# FOTA_Microcontroller_Power_Switch.net
KiCad netlist of a schematic drawn in Altium Designer
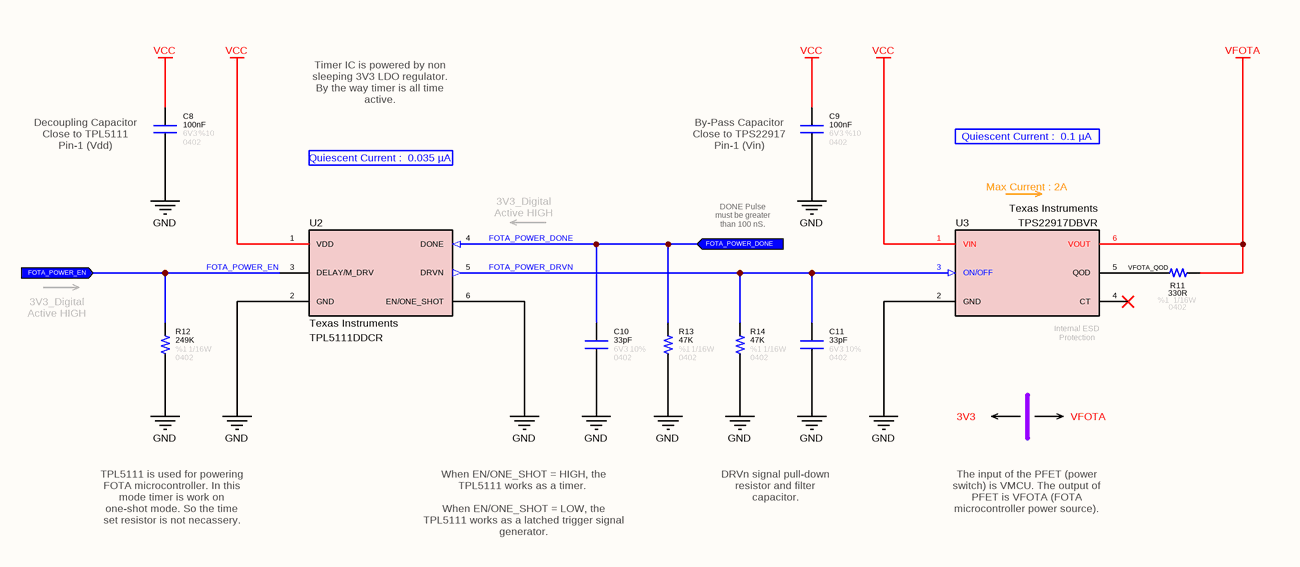
[diagram p0: FOTA Microcontroller Power Switch.SchDoc]

(export (version "E")
  (design (tool "Eeschema 10.0.6"))
  (components
    (comp (ref "C8")
      (value "100nF")
      (footprint "CAPACITOR_0402")
      (description "Capacitor - 100nF [0402-6V3] (Ceramic)")
      (fields
        (field (name "MANUFACTURER PART NUMBER") "04026D104KAT4A")
        (field (name "TOLERANCE") "%10")
        (field (name "VOLTAGE") "6V3")
        (field (name "CASE") "0402")
        (field (name "Comment") "Capacitor - 100nF [0402] (Ceramic)")
      )
      (libsource (lib "P101DA_Library") (part "Capacitor - 100nF [0402-6V3]"))
    )
    (comp (ref "C9")
      (value "100nF")
      (footprint "CAPACITOR_0402")
      (description "Capacitor - 100nF [0402-6V3] (Ceramic)")
      (fields
        (field (name "MANUFACTURER PART NUMBER") "04026D104KAT4A")
        (field (name "TOLERANCE") "%10")
        (field (name "VOLTAGE") "6V3")
        (field (name "CASE") "0402")
        (field (name "Comment") "Capacitor - 100nF [0402] (Ceramic)")
      )
      (libsource (lib "P101DA_Library") (part "Capacitor - 100nF [0402-6V3]"))
    )
    (comp (ref "C10")
      (value "33pF")
      (footprint "CAPACITOR_0402")
      (description "Capacitor - 33pF [0402] (Ceramic)")
      (fields
        (field (name "MANUFACTURER PART NUMBER") "C0402C330J9RACAUTO")
        (field (name "TOLERANCE") "10%")
        (field (name "CASE") "0402")
        (field (name "VOLTAGE") "6V3")
      )
      (libsource (lib "P101DA_Library") (part "Capacitor - 33pF [0402-6V3]"))
    )
    (comp (ref "C11")
      (value "33pF")
      (footprint "CAPACITOR_0402")
      (description "Capacitor - 33pF [0402] (Ceramic)")
      (fields
        (field (name "MANUFACTURER PART NUMBER") "C0402C330J9RACAUTO")
        (field (name "TOLERANCE") "10%")
        (field (name "CASE") "0402")
        (field (name "VOLTAGE") "6V3")
      )
      (libsource (lib "P101DA_Library") (part "Capacitor - 33pF [0402-6V3]"))
    )
    (comp (ref "R11")
      (value "330R")
      (footprint "RESISTOR_0402")
      (description "Thick Film Resistors - SMD 1/16 W 330 Ohm 1%")
      (fields
        (field (name "MANUFACTURER PART NUMBER") "CRCW0402330RFKED")
        (field (name "CASE") "0402")
        (field (name "TOLERANCE") "%1")
        (field (name "POWER") "1/16W")
        (field (name "Comment") "330R - 0402 - %1 - 1/16W")
      )
      (libsource (lib "P101DA_Library") (part "Resistor - 330R [0402]"))
    )
    (comp (ref "R12")
      (value "249K")
      (footprint "RESISTOR_0402")
      (description "Thick Film Resistors - SMD 1/16 W 249 KOhm 1%")
      (fields
        (field (name "MANUFACTURER PART NUMBER") "CRCW0402249KFKED")
        (field (name "POWER") "1/16W")
        (field (name "CASE") "0402")
        (field (name "TOLERANCE") "%1")
        (field (name "Comment") "249K - 0402 - %1 - 1/16W")
      )
      (libsource (lib "P101DA_Library") (part "Resistor - 249K [0402]"))
    )
    (comp (ref "R13")
      (value "47K")
      (footprint "RESISTOR_0402")
      (description "Thick Film Resistors - SMD 1/16 W 47 KOhm 1%")
      (fields
        (field (name "MANUFACTURER PART NUMBER") "CRCW040247K0FKED")
        (field (name "TOLERANCE") "%1")
        (field (name "CASE") "0402")
        (field (name "POWER") "1/16W")
        (field (name "Comment") "47K - 0402 - %1 - 1/16W")
      )
      (libsource (lib "P101DA_Library") (part "Resistor - 47K [0402]"))
    )
    (comp (ref "R14")
      (value "47K")
      (footprint "RESISTOR_0402")
      (description "Thick Film Resistors - SMD 1/16 W 47 KOhm 1%")
      (fields
        (field (name "MANUFACTURER PART NUMBER") "CRCW040247K0FKED")
        (field (name "TOLERANCE") "%1")
        (field (name "CASE") "0402")
        (field (name "POWER") "1/16W")
        (field (name "Comment") "47K - 0402 - %1 - 1/16W")
      )
      (libsource (lib "P101DA_Library") (part "Resistor - 47K [0402]"))
    )
    (comp (ref "U2")
      (value "TPL5111DDCR")
      (footprint "SOT-23-6")
      (description "NANO-POWER SYSTEM TIMER FOR POWE")
      (fields
        (field (name "MANUFACTURER NAME") "Texas Instruments")
        (field (name "MANUFACTURER PART NUMBER") "TPL5111DDCR")
      )
      (libsource (lib "P101DA_Library") (part "IC - TPL5111"))
    )
    (comp (ref "U3")
      (value "Power Switch")
      (footprint "SOT-23-6")
      (description "Power Switch MosFet")
      (fields
        (field (name "MANUFACTURER PART NUMBER") "TPS22917DBVR")
        (field (name "MANUFACTURER NAME") "Texas Instruments")
      )
      (libsource (lib "P101DA_Library") (part "IC - TPS22917"))
    )
  )
  (nets
    (net (code "1") (name "/FOTA_POWER_DONE") (class "Default")
      (node (ref "C10") (pin "2") (pinfunction "2_2") (pintype "passive"))
      (node (ref "R13") (pin "2") (pinfunction "2_2") (pintype "passive"))
      (node (ref "U2") (pin "4") (pinfunction "DONE_4") (pintype "input"))
    )
    (net (code "2") (name "/FOTA_POWER_DRVN") (class "Default")
      (node (ref "C11") (pin "2") (pinfunction "2_2") (pintype "passive"))
      (node (ref "R14") (pin "2") (pinfunction "2_2") (pintype "passive"))
      (node (ref "U2") (pin "5") (pinfunction "DRVN_5") (pintype "output"))
      (node (ref "U3") (pin "3") (pinfunction "ON/OFF_3") (pintype "input"))
    )
    (net (code "3") (name "/FOTA_POWER_EN") (class "Default")
      (node (ref "R12") (pin "2") (pinfunction "2_2") (pintype "passive"))
      (node (ref "U2") (pin "3") (pinfunction "DELAY/M_DRV_3") (pintype "passive"))
    )
    (net (code "4") (name "/VFOTA_QOD") (class "Default")
      (node (ref "R11") (pin "2") (pinfunction "2_2") (pintype "passive"))
      (node (ref "U3") (pin "5") (pinfunction "QOD_5") (pintype "power_in"))
    )
    (net (code "5") (name "GND") (class "Default")
      (node (ref "C10") (pin "1") (pinfunction "1_1") (pintype "passive"))
      (node (ref "C11") (pin "1") (pinfunction "1_1") (pintype "passive"))
      (node (ref "C8") (pin "1") (pinfunction "1_1") (pintype "passive"))
      (node (ref "C9") (pin "1") (pinfunction "1_1") (pintype "passive"))
      (node (ref "R12") (pin "1") (pinfunction "1_1") (pintype "passive"))
      (node (ref "R13") (pin "1") (pinfunction "1_1") (pintype "passive"))
      (node (ref "R14") (pin "1") (pinfunction "1_1") (pintype "passive"))
      (node (ref "U2") (pin "2") (pinfunction "GND_2") (pintype "power_in"))
      (node (ref "U2") (pin "6") (pinfunction "EN/ONE_SHOT_6") (pintype "passive"))
      (node (ref "U3") (pin "2") (pinfunction "GND_2") (pintype "power_in"))
    )
    (net (code "6") (name "VCC") (class "Default")
      (node (ref "C8") (pin "2") (pinfunction "2_2") (pintype "passive"))
      (node (ref "C9") (pin "2") (pinfunction "2_2") (pintype "passive"))
      (node (ref "U2") (pin "1") (pinfunction "VDD_1") (pintype "power_in"))
      (node (ref "U3") (pin "1") (pinfunction "VIN_1") (pintype "power_in"))
    )
    (net (code "7") (name "VFOTA") (class "Default")
      (node (ref "R11") (pin "1") (pinfunction "1_1") (pintype "passive"))
      (node (ref "U3") (pin "6") (pinfunction "VOUT_6") (pintype "power_in"))
    )
    (net (code "8") (name "unconnected-(U3-CT-Pad4)") (class "Default")
      (node (ref "U3") (pin "4") (pinfunction "CT_4") (pintype "power_in+no_connect"))
    )
  )
)
